# Main.net
KiCad netlist of a schematic drawn in Altium Designer
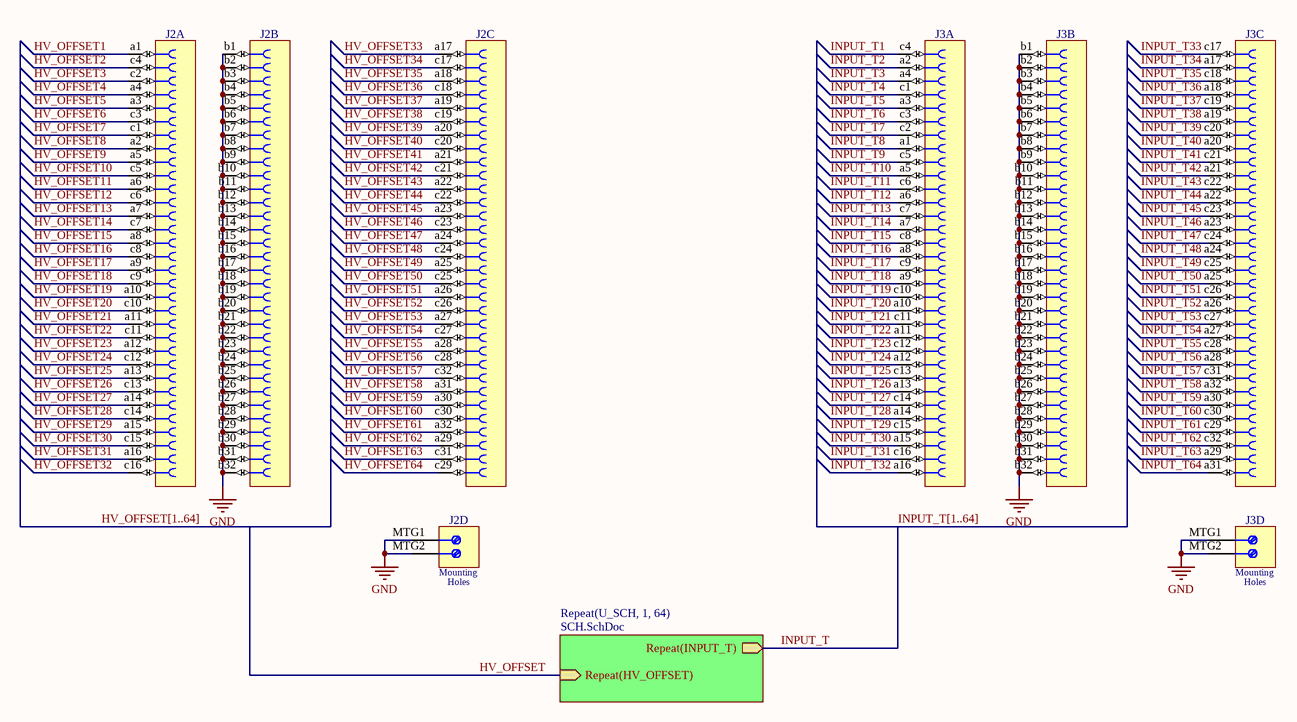
[diagram p0: Main.SchDoc]

(export (version "E")
  (design (tool "Eeschema 10.0.6"))
  (components
    (comp (ref "J2")
      (value "DIN 41612 Type C")
      (footprint "HARTING_09 03 296 6861")
      (description "Connector 96abc Female (3x32)")
      (fields
        (field (name "PART NUMBER") "HARTING_09 03 296 6861")
        (field (name "MANUFACTURER") "HARTING")
        (field (name "AUTHOR") "CERN DEM JLC")
      )
      (libsource (lib "") (part "Connector 96abc Female (3x32)_1"))
    )
    (comp (ref "J3")
      (value "DIN 41612 Type C")
      (footprint "HARTING_09 03 296 6861")
      (description "Connector 96abc Female (3x32)")
      (fields
        (field (name "PART NUMBER") "HARTING_09 03 296 6861")
        (field (name "MANUFACTURER") "HARTING")
        (field (name "AUTHOR") "CERN DEM JLC")
      )
      (libsource (lib "") (part "Connector 96abc Female (3x32)_3"))
    )
  )
  (nets
    (net (code "2") (name "/HV_OFFSET1") (class "Default")
      (node (ref "J2") (pin "a1") (pinfunction "a1_a1") (pintype "bidirectional"))
    )
    (net (code "3") (name "/HV_OFFSET2") (class "Default")
      (node (ref "J2") (pin "c4") (pinfunction "c4_c4") (pintype "bidirectional"))
    )
    (net (code "4") (name "/HV_OFFSET3") (class "Default")
      (node (ref "J2") (pin "c2") (pinfunction "c2_c2") (pintype "bidirectional"))
    )
    (net (code "5") (name "/HV_OFFSET4") (class "Default")
      (node (ref "J2") (pin "a4") (pinfunction "a4_a4") (pintype "bidirectional"))
    )
    (net (code "6") (name "/HV_OFFSET5") (class "Default")
      (node (ref "J2") (pin "a3") (pinfunction "a3_a3") (pintype "bidirectional"))
    )
    (net (code "7") (name "/HV_OFFSET6") (class "Default")
      (node (ref "J2") (pin "c3") (pinfunction "c3_c3") (pintype "bidirectional"))
    )
    (net (code "8") (name "/HV_OFFSET7") (class "Default")
      (node (ref "J2") (pin "c1") (pinfunction "c1_c1") (pintype "bidirectional"))
    )
    (net (code "9") (name "/HV_OFFSET8") (class "Default")
      (node (ref "J2") (pin "a2") (pinfunction "a2_a2") (pintype "bidirectional"))
    )
    (net (code "10") (name "/HV_OFFSET9") (class "Default")
      (node (ref "J2") (pin "a5") (pinfunction "a5_a5") (pintype "bidirectional"))
    )
    (net (code "11") (name "/HV_OFFSET10") (class "Default")
      (node (ref "J2") (pin "c5") (pinfunction "c5_c5") (pintype "bidirectional"))
    )
    (net (code "12") (name "/HV_OFFSET11") (class "Default")
      (node (ref "J2") (pin "a6") (pinfunction "a6_a6") (pintype "bidirectional"))
    )
    (net (code "13") (name "/HV_OFFSET12") (class "Default")
      (node (ref "J2") (pin "c6") (pinfunction "c6_c6") (pintype "bidirectional"))
    )
    (net (code "14") (name "/HV_OFFSET13") (class "Default")
      (node (ref "J2") (pin "a7") (pinfunction "a7_a7") (pintype "bidirectional"))
    )
    (net (code "15") (name "/HV_OFFSET14") (class "Default")
      (node (ref "J2") (pin "c7") (pinfunction "c7_c7") (pintype "bidirectional"))
    )
    (net (code "16") (name "/HV_OFFSET15") (class "Default")
      (node (ref "J2") (pin "a8") (pinfunction "a8_a8") (pintype "bidirectional"))
    )
    (net (code "17") (name "/HV_OFFSET16") (class "Default")
      (node (ref "J2") (pin "c8") (pinfunction "c8_c8") (pintype "bidirectional"))
    )
    (net (code "18") (name "/HV_OFFSET17") (class "Default")
      (node (ref "J2") (pin "a9") (pinfunction "a9_a9") (pintype "bidirectional"))
    )
    (net (code "19") (name "/HV_OFFSET18") (class "Default")
      (node (ref "J2") (pin "c9") (pinfunction "c9_c9") (pintype "bidirectional"))
    )
    (net (code "20") (name "/HV_OFFSET19") (class "Default")
      (node (ref "J2") (pin "a10") (pinfunction "a10_a10") (pintype "bidirectional"))
    )
    (net (code "21") (name "/HV_OFFSET20") (class "Default")
      (node (ref "J2") (pin "c10") (pinfunction "c10_c10") (pintype "bidirectional"))
    )
    (net (code "22") (name "/HV_OFFSET21") (class "Default")
      (node (ref "J2") (pin "a11") (pinfunction "a11_a11") (pintype "bidirectional"))
    )
    (net (code "23") (name "/HV_OFFSET22") (class "Default")
      (node (ref "J2") (pin "c11") (pinfunction "c11_c11") (pintype "bidirectional"))
    )
    (net (code "24") (name "/HV_OFFSET23") (class "Default")
      (node (ref "J2") (pin "a12") (pinfunction "a12_a12") (pintype "bidirectional"))
    )
    (net (code "25") (name "/HV_OFFSET24") (class "Default")
      (node (ref "J2") (pin "c12") (pinfunction "c12_c12") (pintype "bidirectional"))
    )
    (net (code "26") (name "/HV_OFFSET25") (class "Default")
      (node (ref "J2") (pin "a13") (pinfunction "a13_a13") (pintype "bidirectional"))
    )
    (net (code "27") (name "/HV_OFFSET26") (class "Default")
      (node (ref "J2") (pin "c13") (pinfunction "c13_c13") (pintype "bidirectional"))
    )
    (net (code "28") (name "/HV_OFFSET27") (class "Default")
      (node (ref "J2") (pin "a14") (pinfunction "a14_a14") (pintype "bidirectional"))
    )
    (net (code "29") (name "/HV_OFFSET28") (class "Default")
      (node (ref "J2") (pin "c14") (pinfunction "c14_c14") (pintype "bidirectional"))
    )
    (net (code "30") (name "/HV_OFFSET29") (class "Default")
      (node (ref "J2") (pin "a15") (pinfunction "a15_a15") (pintype "bidirectional"))
    )
    (net (code "31") (name "/HV_OFFSET30") (class "Default")
      (node (ref "J2") (pin "c15") (pinfunction "c15_c15") (pintype "bidirectional"))
    )
    (net (code "32") (name "/HV_OFFSET31") (class "Default")
      (node (ref "J2") (pin "a16") (pinfunction "a16_a16") (pintype "bidirectional"))
    )
    (net (code "33") (name "/HV_OFFSET32") (class "Default")
      (node (ref "J2") (pin "c16") (pinfunction "c16_c16") (pintype "bidirectional"))
    )
    (net (code "34") (name "/HV_OFFSET33") (class "Default")
      (node (ref "J2") (pin "a17") (pinfunction "a17_a17") (pintype "bidirectional"))
    )
    (net (code "35") (name "/HV_OFFSET34") (class "Default")
      (node (ref "J2") (pin "c17") (pinfunction "c17_c17") (pintype "bidirectional"))
    )
    (net (code "36") (name "/HV_OFFSET35") (class "Default")
      (node (ref "J2") (pin "a18") (pinfunction "a18_a18") (pintype "bidirectional"))
    )
    (net (code "37") (name "/HV_OFFSET36") (class "Default")
      (node (ref "J2") (pin "c18") (pinfunction "c18_c18") (pintype "bidirectional"))
    )
    (net (code "38") (name "/HV_OFFSET37") (class "Default")
      (node (ref "J2") (pin "a19") (pinfunction "a19_a19") (pintype "bidirectional"))
    )
    (net (code "39") (name "/HV_OFFSET38") (class "Default")
      (node (ref "J2") (pin "c19") (pinfunction "c19_c19") (pintype "bidirectional"))
    )
    (net (code "40") (name "/HV_OFFSET39") (class "Default")
      (node (ref "J2") (pin "a20") (pinfunction "a20_a20") (pintype "bidirectional"))
    )
    (net (code "41") (name "/HV_OFFSET40") (class "Default")
      (node (ref "J2") (pin "c20") (pinfunction "c20_c20") (pintype "bidirectional"))
    )
    (net (code "42") (name "/HV_OFFSET41") (class "Default")
      (node (ref "J2") (pin "a21") (pinfunction "a21_a21") (pintype "bidirectional"))
    )
    (net (code "43") (name "/HV_OFFSET42") (class "Default")
      (node (ref "J2") (pin "c21") (pinfunction "c21_c21") (pintype "bidirectional"))
    )
    (net (code "44") (name "/HV_OFFSET43") (class "Default")
      (node (ref "J2") (pin "a22") (pinfunction "a22_a22") (pintype "bidirectional"))
    )
    (net (code "45") (name "/HV_OFFSET44") (class "Default")
      (node (ref "J2") (pin "c22") (pinfunction "c22_c22") (pintype "bidirectional"))
    )
    (net (code "46") (name "/HV_OFFSET45") (class "Default")
      (node (ref "J2") (pin "a23") (pinfunction "a23_a23") (pintype "bidirectional"))
    )
    (net (code "47") (name "/HV_OFFSET46") (class "Default")
      (node (ref "J2") (pin "c23") (pinfunction "c23_c23") (pintype "bidirectional"))
    )
    (net (code "48") (name "/HV_OFFSET47") (class "Default")
      (node (ref "J2") (pin "a24") (pinfunction "a24_a24") (pintype "bidirectional"))
    )
    (net (code "49") (name "/HV_OFFSET48") (class "Default")
      (node (ref "J2") (pin "c24") (pinfunction "c24_c24") (pintype "bidirectional"))
    )
    (net (code "50") (name "/HV_OFFSET49") (class "Default")
      (node (ref "J2") (pin "a25") (pinfunction "a25_a25") (pintype "bidirectional"))
    )
    (net (code "51") (name "/HV_OFFSET50") (class "Default")
      (node (ref "J2") (pin "c25") (pinfunction "c25_c25") (pintype "bidirectional"))
    )
    (net (code "52") (name "/HV_OFFSET51") (class "Default")
      (node (ref "J2") (pin "a26") (pinfunction "a26_a26") (pintype "bidirectional"))
    )
    (net (code "53") (name "/HV_OFFSET52") (class "Default")
      (node (ref "J2") (pin "c26") (pinfunction "c26_c26") (pintype "bidirectional"))
    )
    (net (code "54") (name "/HV_OFFSET53") (class "Default")
      (node (ref "J2") (pin "a27") (pinfunction "a27_a27") (pintype "bidirectional"))
    )
    (net (code "55") (name "/HV_OFFSET54") (class "Default")
      (node (ref "J2") (pin "c27") (pinfunction "c27_c27") (pintype "bidirectional"))
    )
    (net (code "56") (name "/HV_OFFSET55") (class "Default")
      (node (ref "J2") (pin "a28") (pinfunction "a28_a28") (pintype "bidirectional"))
    )
    (net (code "57") (name "/HV_OFFSET56") (class "Default")
      (node (ref "J2") (pin "c28") (pinfunction "c28_c28") (pintype "bidirectional"))
    )
    (net (code "58") (name "/HV_OFFSET57") (class "Default")
      (node (ref "J2") (pin "c32") (pinfunction "c32_c32") (pintype "bidirectional"))
    )
    (net (code "59") (name "/HV_OFFSET58") (class "Default")
      (node (ref "J2") (pin "a31") (pinfunction "a31_a31") (pintype "bidirectional"))
    )
    (net (code "60") (name "/HV_OFFSET59") (class "Default")
      (node (ref "J2") (pin "a30") (pinfunction "a30_a30") (pintype "bidirectional"))
    )
    (net (code "61") (name "/HV_OFFSET60") (class "Default")
      (node (ref "J2") (pin "c30") (pinfunction "c30_c30") (pintype "bidirectional"))
    )
    (net (code "62") (name "/HV_OFFSET61") (class "Default")
      (node (ref "J2") (pin "a32") (pinfunction "a32_a32") (pintype "bidirectional"))
    )
    (net (code "63") (name "/HV_OFFSET62") (class "Default")
      (node (ref "J2") (pin "a29") (pinfunction "a29_a29") (pintype "bidirectional"))
    )
    (net (code "64") (name "/HV_OFFSET63") (class "Default")
      (node (ref "J2") (pin "c31") (pinfunction "c31_c31") (pintype "bidirectional"))
    )
    (net (code "65") (name "/HV_OFFSET64") (class "Default")
      (node (ref "J2") (pin "c29") (pinfunction "c29_c29") (pintype "bidirectional"))
    )
    (net (code "68") (name "/INPUT_T1") (class "Default")
      (node (ref "J3") (pin "c4") (pinfunction "c4_c4") (pintype "bidirectional"))
    )
    (net (code "69") (name "/INPUT_T2") (class "Default")
      (node (ref "J3") (pin "a2") (pinfunction "a2_a2") (pintype "bidirectional"))
    )
    (net (code "70") (name "/INPUT_T3") (class "Default")
      (node (ref "J3") (pin "a4") (pinfunction "a4_a4") (pintype "bidirectional"))
    )
    (net (code "71") (name "/INPUT_T4") (class "Default")
      (node (ref "J3") (pin "c1") (pinfunction "c1_c1") (pintype "bidirectional"))
    )
    (net (code "72") (name "/INPUT_T5") (class "Default")
      (node (ref "J3") (pin "a3") (pinfunction "a3_a3") (pintype "bidirectional"))
    )
    (net (code "73") (name "/INPUT_T6") (class "Default")
      (node (ref "J3") (pin "c3") (pinfunction "c3_c3") (pintype "bidirectional"))
    )
    (net (code "74") (name "/INPUT_T7") (class "Default")
      (node (ref "J3") (pin "c2") (pinfunction "c2_c2") (pintype "bidirectional"))
    )
    (net (code "75") (name "/INPUT_T8") (class "Default")
      (node (ref "J3") (pin "a1") (pinfunction "a1_a1") (pintype "bidirectional"))
    )
    (net (code "76") (name "/INPUT_T9") (class "Default")
      (node (ref "J3") (pin "c5") (pinfunction "c5_c5") (pintype "bidirectional"))
    )
    (net (code "77") (name "/INPUT_T10") (class "Default")
      (node (ref "J3") (pin "a5") (pinfunction "a5_a5") (pintype "bidirectional"))
    )
    (net (code "78") (name "/INPUT_T11") (class "Default")
      (node (ref "J3") (pin "c6") (pinfunction "c6_c6") (pintype "bidirectional"))
    )
    (net (code "79") (name "/INPUT_T12") (class "Default")
      (node (ref "J3") (pin "a6") (pinfunction "a6_a6") (pintype "bidirectional"))
    )
    (net (code "80") (name "/INPUT_T13") (class "Default")
      (node (ref "J3") (pin "c7") (pinfunction "c7_c7") (pintype "bidirectional"))
    )
    (net (code "81") (name "/INPUT_T14") (class "Default")
      (node (ref "J3") (pin "a7") (pinfunction "a7_a7") (pintype "bidirectional"))
    )
    (net (code "82") (name "/INPUT_T15") (class "Default")
      (node (ref "J3") (pin "c8") (pinfunction "c8_c8") (pintype "bidirectional"))
    )
    (net (code "83") (name "/INPUT_T16") (class "Default")
      (node (ref "J3") (pin "a8") (pinfunction "a8_a8") (pintype "bidirectional"))
    )
    (net (code "84") (name "/INPUT_T17") (class "Default")
      (node (ref "J3") (pin "c9") (pinfunction "c9_c9") (pintype "bidirectional"))
    )
    (net (code "85") (name "/INPUT_T18") (class "Default")
      (node (ref "J3") (pin "a9") (pinfunction "a9_a9") (pintype "bidirectional"))
    )
    (net (code "86") (name "/INPUT_T19") (class "Default")
      (node (ref "J3") (pin "c10") (pinfunction "c10_c10") (pintype "bidirectional"))
    )
    (net (code "87") (name "/INPUT_T20") (class "Default")
      (node (ref "J3") (pin "a10") (pinfunction "a10_a10") (pintype "bidirectional"))
    )
    (net (code "88") (name "/INPUT_T21") (class "Default")
      (node (ref "J3") (pin "c11") (pinfunction "c11_c11") (pintype "bidirectional"))
    )
    (net (code "89") (name "/INPUT_T22") (class "Default")
      (node (ref "J3") (pin "a11") (pinfunction "a11_a11") (pintype "bidirectional"))
    )
    (net (code "90") (name "/INPUT_T23") (class "Default")
      (node (ref "J3") (pin "c12") (pinfunction "c12_c12") (pintype "bidirectional"))
    )
    (net (code "91") (name "/INPUT_T24") (class "Default")
      (node (ref "J3") (pin "a12") (pinfunction "a12_a12") (pintype "bidirectional"))
    )
    (net (code "92") (name "/INPUT_T25") (class "Default")
      (node (ref "J3") (pin "c13") (pinfunction "c13_c13") (pintype "bidirectional"))
    )
    (net (code "93") (name "/INPUT_T26") (class "Default")
      (node (ref "J3") (pin "a13") (pinfunction "a13_a13") (pintype "bidirectional"))
    )
    (net (code "94") (name "/INPUT_T27") (class "Default")
      (node (ref "J3") (pin "c14") (pinfunction "c14_c14") (pintype "bidirectional"))
    )
    (net (code "95") (name "/INPUT_T28") (class "Default")
      (node (ref "J3") (pin "a14") (pinfunction "a14_a14") (pintype "bidirectional"))
    )
    (net (code "96") (name "/INPUT_T29") (class "Default")
      (node (ref "J3") (pin "c15") (pinfunction "c15_c15") (pintype "bidirectional"))
    )
    (net (code "97") (name "/INPUT_T30") (class "Default")
      (node (ref "J3") (pin "a15") (pinfunction "a15_a15") (pintype "bidirectional"))
    )
    (net (code "98") (name "/INPUT_T31") (class "Default")
      (node (ref "J3") (pin "c16") (pinfunction "c16_c16") (pintype "bidirectional"))
    )
    (net (code "99") (name "/INPUT_T32") (class "Default")
      (node (ref "J3") (pin "a16") (pinfunction "a16_a16") (pintype "bidirectional"))
    )
    (net (code "100") (name "/INPUT_T33") (class "Default")
      (node (ref "J3") (pin "c17") (pinfunction "c17_c17") (pintype "bidirectional"))
    )
    (net (code "101") (name "/INPUT_T34") (class "Default")
      (node (ref "J3") (pin "a17") (pinfunction "a17_a17") (pintype "bidirectional"))
    )
    (net (code "102") (name "/INPUT_T35") (class "Default")
      (node (ref "J3") (pin "c18") (pinfunction "c18_c18") (pintype "bidirectional"))
    )
    (net (code "103") (name "/INPUT_T36") (class "Default")
      (node (ref "J3") (pin "a18") (pinfunction "a18_a18") (pintype "bidirectional"))
    )
    (net (code "104") (name "/INPUT_T37") (class "Default")
      (node (ref "J3") (pin "c19") (pinfunction "c19_c19") (pintype "bidirectional"))
    )
    (net (code "105") (name "/INPUT_T38") (class "Default")
      (node (ref "J3") (pin "a19") (pinfunction "a19_a19") (pintype "bidirectional"))
    )
    (net (code "106") (name "/INPUT_T39") (class "Default")
      (node (ref "J3") (pin "c20") (pinfunction "c20_c20") (pintype "bidirectional"))
    )
    (net (code "107") (name "/INPUT_T40") (class "Default")
      (node (ref "J3") (pin "a20") (pinfunction "a20_a20") (pintype "bidirectional"))
    )
    (net (code "108") (name "/INPUT_T41") (class "Default")
      (node (ref "J3") (pin "c21") (pinfunction "c21_c21") (pintype "bidirectional"))
    )
    (net (code "109") (name "/INPUT_T42") (class "Default")
      (node (ref "J3") (pin "a21") (pinfunction "a21_a21") (pintype "bidirectional"))
    )
    (net (code "110") (name "/INPUT_T43") (class "Default")
      (node (ref "J3") (pin "c22") (pinfunction "c22_c22") (pintype "bidirectional"))
    )
    (net (code "111") (name "/INPUT_T44") (class "Default")
      (node (ref "J3") (pin "a22") (pinfunction "a22_a22") (pintype "bidirectional"))
    )
    (net (code "112") (name "/INPUT_T45") (class "Default")
      (node (ref "J3") (pin "c23") (pinfunction "c23_c23") (pintype "bidirectional"))
    )
    (net (code "113") (name "/INPUT_T46") (class "Default")
      (node (ref "J3") (pin "a23") (pinfunction "a23_a23") (pintype "bidirectional"))
    )
    (net (code "114") (name "/INPUT_T47") (class "Default")
      (node (ref "J3") (pin "c24") (pinfunction "c24_c24") (pintype "bidirectional"))
    )
    (net (code "115") (name "/INPUT_T48") (class "Default")
      (node (ref "J3") (pin "a24") (pinfunction "a24_a24") (pintype "bidirectional"))
    )
    (net (code "116") (name "/INPUT_T49") (class "Default")
      (node (ref "J3") (pin "c25") (pinfunction "c25_c25") (pintype "bidirectional"))
    )
    (net (code "117") (name "/INPUT_T50") (class "Default")
      (node (ref "J3") (pin "a25") (pinfunction "a25_a25") (pintype "bidirectional"))
    )
    (net (code "118") (name "/INPUT_T51") (class "Default")
      (node (ref "J3") (pin "c26") (pinfunction "c26_c26") (pintype "bidirectional"))
    )
    (net (code "119") (name "/INPUT_T52") (class "Default")
      (node (ref "J3") (pin "a26") (pinfunction "a26_a26") (pintype "bidirectional"))
    )
    (net (code "120") (name "/INPUT_T53") (class "Default")
      (node (ref "J3") (pin "c27") (pinfunction "c27_c27") (pintype "bidirectional"))
    )
    (net (code "121") (name "/INPUT_T54") (class "Default")
      (node (ref "J3") (pin "a27") (pinfunction "a27_a27") (pintype "bidirectional"))
    )
    (net (code "122") (name "/INPUT_T55") (class "Default")
      (node (ref "J3") (pin "c28") (pinfunction "c28_c28") (pintype "bidirectional"))
    )
    (net (code "123") (name "/INPUT_T56") (class "Default")
      (node (ref "J3") (pin "a28") (pinfunction "a28_a28") (pintype "bidirectional"))
    )
    (net (code "124") (name "/INPUT_T57") (class "Default")
      (node (ref "J3") (pin "c31") (pinfunction "c31_c31") (pintype "bidirectional"))
    )
    (net (code "125") (name "/INPUT_T58") (class "Default")
      (node (ref "J3") (pin "a32") (pinfunction "a32_a32") (pintype "bidirectional"))
    )
    (net (code "126") (name "/INPUT_T59") (class "Default")
      (node (ref "J3") (pin "a30") (pinfunction "a30_a30") (pintype "bidirectional"))
    )
    (net (code "127") (name "/INPUT_T60") (class "Default")
      (node (ref "J3") (pin "c30") (pinfunction "c30_c30") (pintype "bidirectional"))
    )
    (net (code "128") (name "/INPUT_T61") (class "Default")
      (node (ref "J3") (pin "c29") (pinfunction "c29_c29") (pintype "bidirectional"))
    )
    (net (code "129") (name "/INPUT_T62") (class "Default")
      (node (ref "J3") (pin "c32") (pinfunction "c32_c32") (pintype "bidirectional"))
    )
    (net (code "130") (name "/INPUT_T63") (class "Default")
      (node (ref "J3") (pin "a29") (pinfunction "a29_a29") (pintype "bidirectional"))
    )
    (net (code "131") (name "/INPUT_T64") (class "Default")
      (node (ref "J3") (pin "a31") (pinfunction "a31_a31") (pintype "bidirectional"))
    )
    (net (code "133") (name "GND") (class "Default")
      (node (ref "J2") (pin "MTG1") (pinfunction "MTG1_MTG1") (pintype "passive"))
      (node (ref "J2") (pin "MTG2") (pinfunction "MTG2_MTG2") (pintype "passive"))
      (node (ref "J2") (pin "b1") (pinfunction "b1_b1") (pintype "bidirectional"))
      (node (ref "J2") (pin "b10") (pinfunction "b10_b10") (pintype "bidirectional"))
      (node (ref "J2") (pin "b11") (pinfunction "b11_b11") (pintype "bidirectional"))
      (node (ref "J2") (pin "b12") (pinfunction "b12_b12") (pintype "bidirectional"))
      (node (ref "J2") (pin "b13") (pinfunction "b13_b13") (pintype "bidirectional"))
      (node (ref "J2") (pin "b14") (pinfunction "b14_b14") (pintype "bidirectional"))
      (node (ref "J2") (pin "b15") (pinfunction "b15_b15") (pintype "bidirectional"))
      (node (ref "J2") (pin "b16") (pinfunction "b16_b16") (pintype "bidirectional"))
      (node (ref "J2") (pin "b17") (pinfunction "b17_b17") (pintype "bidirectional"))
      (node (ref "J2") (pin "b18") (pinfunction "b18_b18") (pintype "bidirectional"))
      (node (ref "J2") (pin "b19") (pinfunction "b19_b19") (pintype "bidirectional"))
      (node (ref "J2") (pin "b2") (pinfunction "b2_b2") (pintype "bidirectional"))
      (node (ref "J2") (pin "b20") (pinfunction "b20_b20") (pintype "bidirectional"))
      (node (ref "J2") (pin "b21") (pinfunction "b21_b21") (pintype "bidirectional"))
      (node (ref "J2") (pin "b22") (pinfunction "b22_b22") (pintype "bidirectional"))
      (node (ref "J2") (pin "b23") (pinfunction "b23_b23") (pintype "bidirectional"))
      (node (ref "J2") (pin "b24") (pinfunction "b24_b24") (pintype "bidirectional"))
      (node (ref "J2") (pin "b25") (pinfunction "b25_b25") (pintype "bidirectional"))
      (node (ref "J2") (pin "b26") (pinfunction "b26_b26") (pintype "bidirectional"))
      (node (ref "J2") (pin "b27") (pinfunction "b27_b27") (pintype "bidirectional"))
      (node (ref "J2") (pin "b28") (pinfunction "b28_b28") (pintype "bidirectional"))
      (node (ref "J2") (pin "b29") (pinfunction "b29_b29") (pintype "bidirectional"))
      (node (ref "J2") (pin "b3") (pinfunction "b3_b3") (pintype "bidirectional"))
      (node (ref "J2") (pin "b30") (pinfunction "b30_b30") (pintype "bidirectional"))
      (node (ref "J2") (pin "b31") (pinfunction "b31_b31") (pintype "bidirectional"))
      (node (ref "J2") (pin "b32") (pinfunction "b32_b32") (pintype "bidirectional"))
      (node (ref "J2") (pin "b4") (pinfunction "b4_b4") (pintype "bidirectional"))
      (node (ref "J2") (pin "b5") (pinfunction "b5_b5") (pintype "bidirectional"))
      (node (ref "J2") (pin "b6") (pinfunction "b6_b6") (pintype "bidirectional"))
      (node (ref "J2") (pin "b7") (pinfunction "b7_b7") (pintype "bidirectional"))
      (node (ref "J2") (pin "b8") (pinfunction "b8_b8") (pintype "bidirectional"))
      (node (ref "J2") (pin "b9") (pinfunction "b9_b9") (pintype "bidirectional"))
      (node (ref "J3") (pin "MTG1") (pinfunction "MTG1_MTG1") (pintype "passive"))
      (node (ref "J3") (pin "MTG2") (pinfunction "MTG2_MTG2") (pintype "passive"))
      (node (ref "J3") (pin "b1") (pinfunction "b1_b1") (pintype "bidirectional"))
      (node (ref "J3") (pin "b10") (pinfunction "b10_b10") (pintype "bidirectional"))
      (node (ref "J3") (pin "b11") (pinfunction "b11_b11") (pintype "bidirectional"))
      (node (ref "J3") (pin "b12") (pinfunction "b12_b12") (pintype "bidirectional"))
      (node (ref "J3") (pin "b13") (pinfunction "b13_b13") (pintype "bidirectional"))
      (node (ref "J3") (pin "b14") (pinfunction "b14_b14") (pintype "bidirectional"))
      (node (ref "J3") (pin "b15") (pinfunction "b15_b15") (pintype "bidirectional"))
      (node (ref "J3") (pin "b16") (pinfunction "b16_b16") (pintype "bidirectional"))
      (node (ref "J3") (pin "b17") (pinfunction "b17_b17") (pintype "bidirectional"))
      (node (ref "J3") (pin "b18") (pinfunction "b18_b18") (pintype "bidirectional"))
      (node (ref "J3") (pin "b19") (pinfunction "b19_b19") (pintype "bidirectional"))
      (node (ref "J3") (pin "b2") (pinfunction "b2_b2") (pintype "bidirectional"))
      (node (ref "J3") (pin "b20") (pinfunction "b20_b20") (pintype "bidirectional"))
      (node (ref "J3") (pin "b21") (pinfunction "b21_b21") (pintype "bidirectional"))
      (node (ref "J3") (pin "b22") (pinfunction "b22_b22") (pintype "bidirectional"))
      (node (ref "J3") (pin "b23") (pinfunction "b23_b23") (pintype "bidirectional"))
      (node (ref "J3") (pin "b24") (pinfunction "b24_b24") (pintype "bidirectional"))
      (node (ref "J3") (pin "b25") (pinfunction "b25_b25") (pintype "bidirectional"))
      (node (ref "J3") (pin "b26") (pinfunction "b26_b26") (pintype "bidirectional"))
      (node (ref "J3") (pin "b27") (pinfunction "b27_b27") (pintype "bidirectional"))
      (node (ref "J3") (pin "b28") (pinfunction "b28_b28") (pintype "bidirectional"))
      (node (ref "J3") (pin "b29") (pinfunction "b29_b29") (pintype "bidirectional"))
      (node (ref "J3") (pin "b3") (pinfunction "b3_b3") (pintype "bidirectional"))
      (node (ref "J3") (pin "b30") (pinfunction "b30_b30") (pintype "bidirectional"))
      (node (ref "J3") (pin "b31") (pinfunction "b31_b31") (pintype "bidirectional"))
      (node (ref "J3") (pin "b32") (pinfunction "b32_b32") (pintype "bidirectional"))
      (node (ref "J3") (pin "b4") (pinfunction "b4_b4") (pintype "bidirectional"))
      (node (ref "J3") (pin "b5") (pinfunction "b5_b5") (pintype "bidirectional"))
      (node (ref "J3") (pin "b6") (pinfunction "b6_b6") (pintype "bidirectional"))
      (node (ref "J3") (pin "b7") (pinfunction "b7_b7") (pintype "bidirectional"))
      (node (ref "J3") (pin "b8") (pinfunction "b8_b8") (pintype "bidirectional"))
      (node (ref "J3") (pin "b9") (pinfunction "b9_b9") (pintype "bidirectional"))
    )
  )
)
